# EasyEDA_Source.net
KiCad netlist of a schematic drawn in EasyEDA
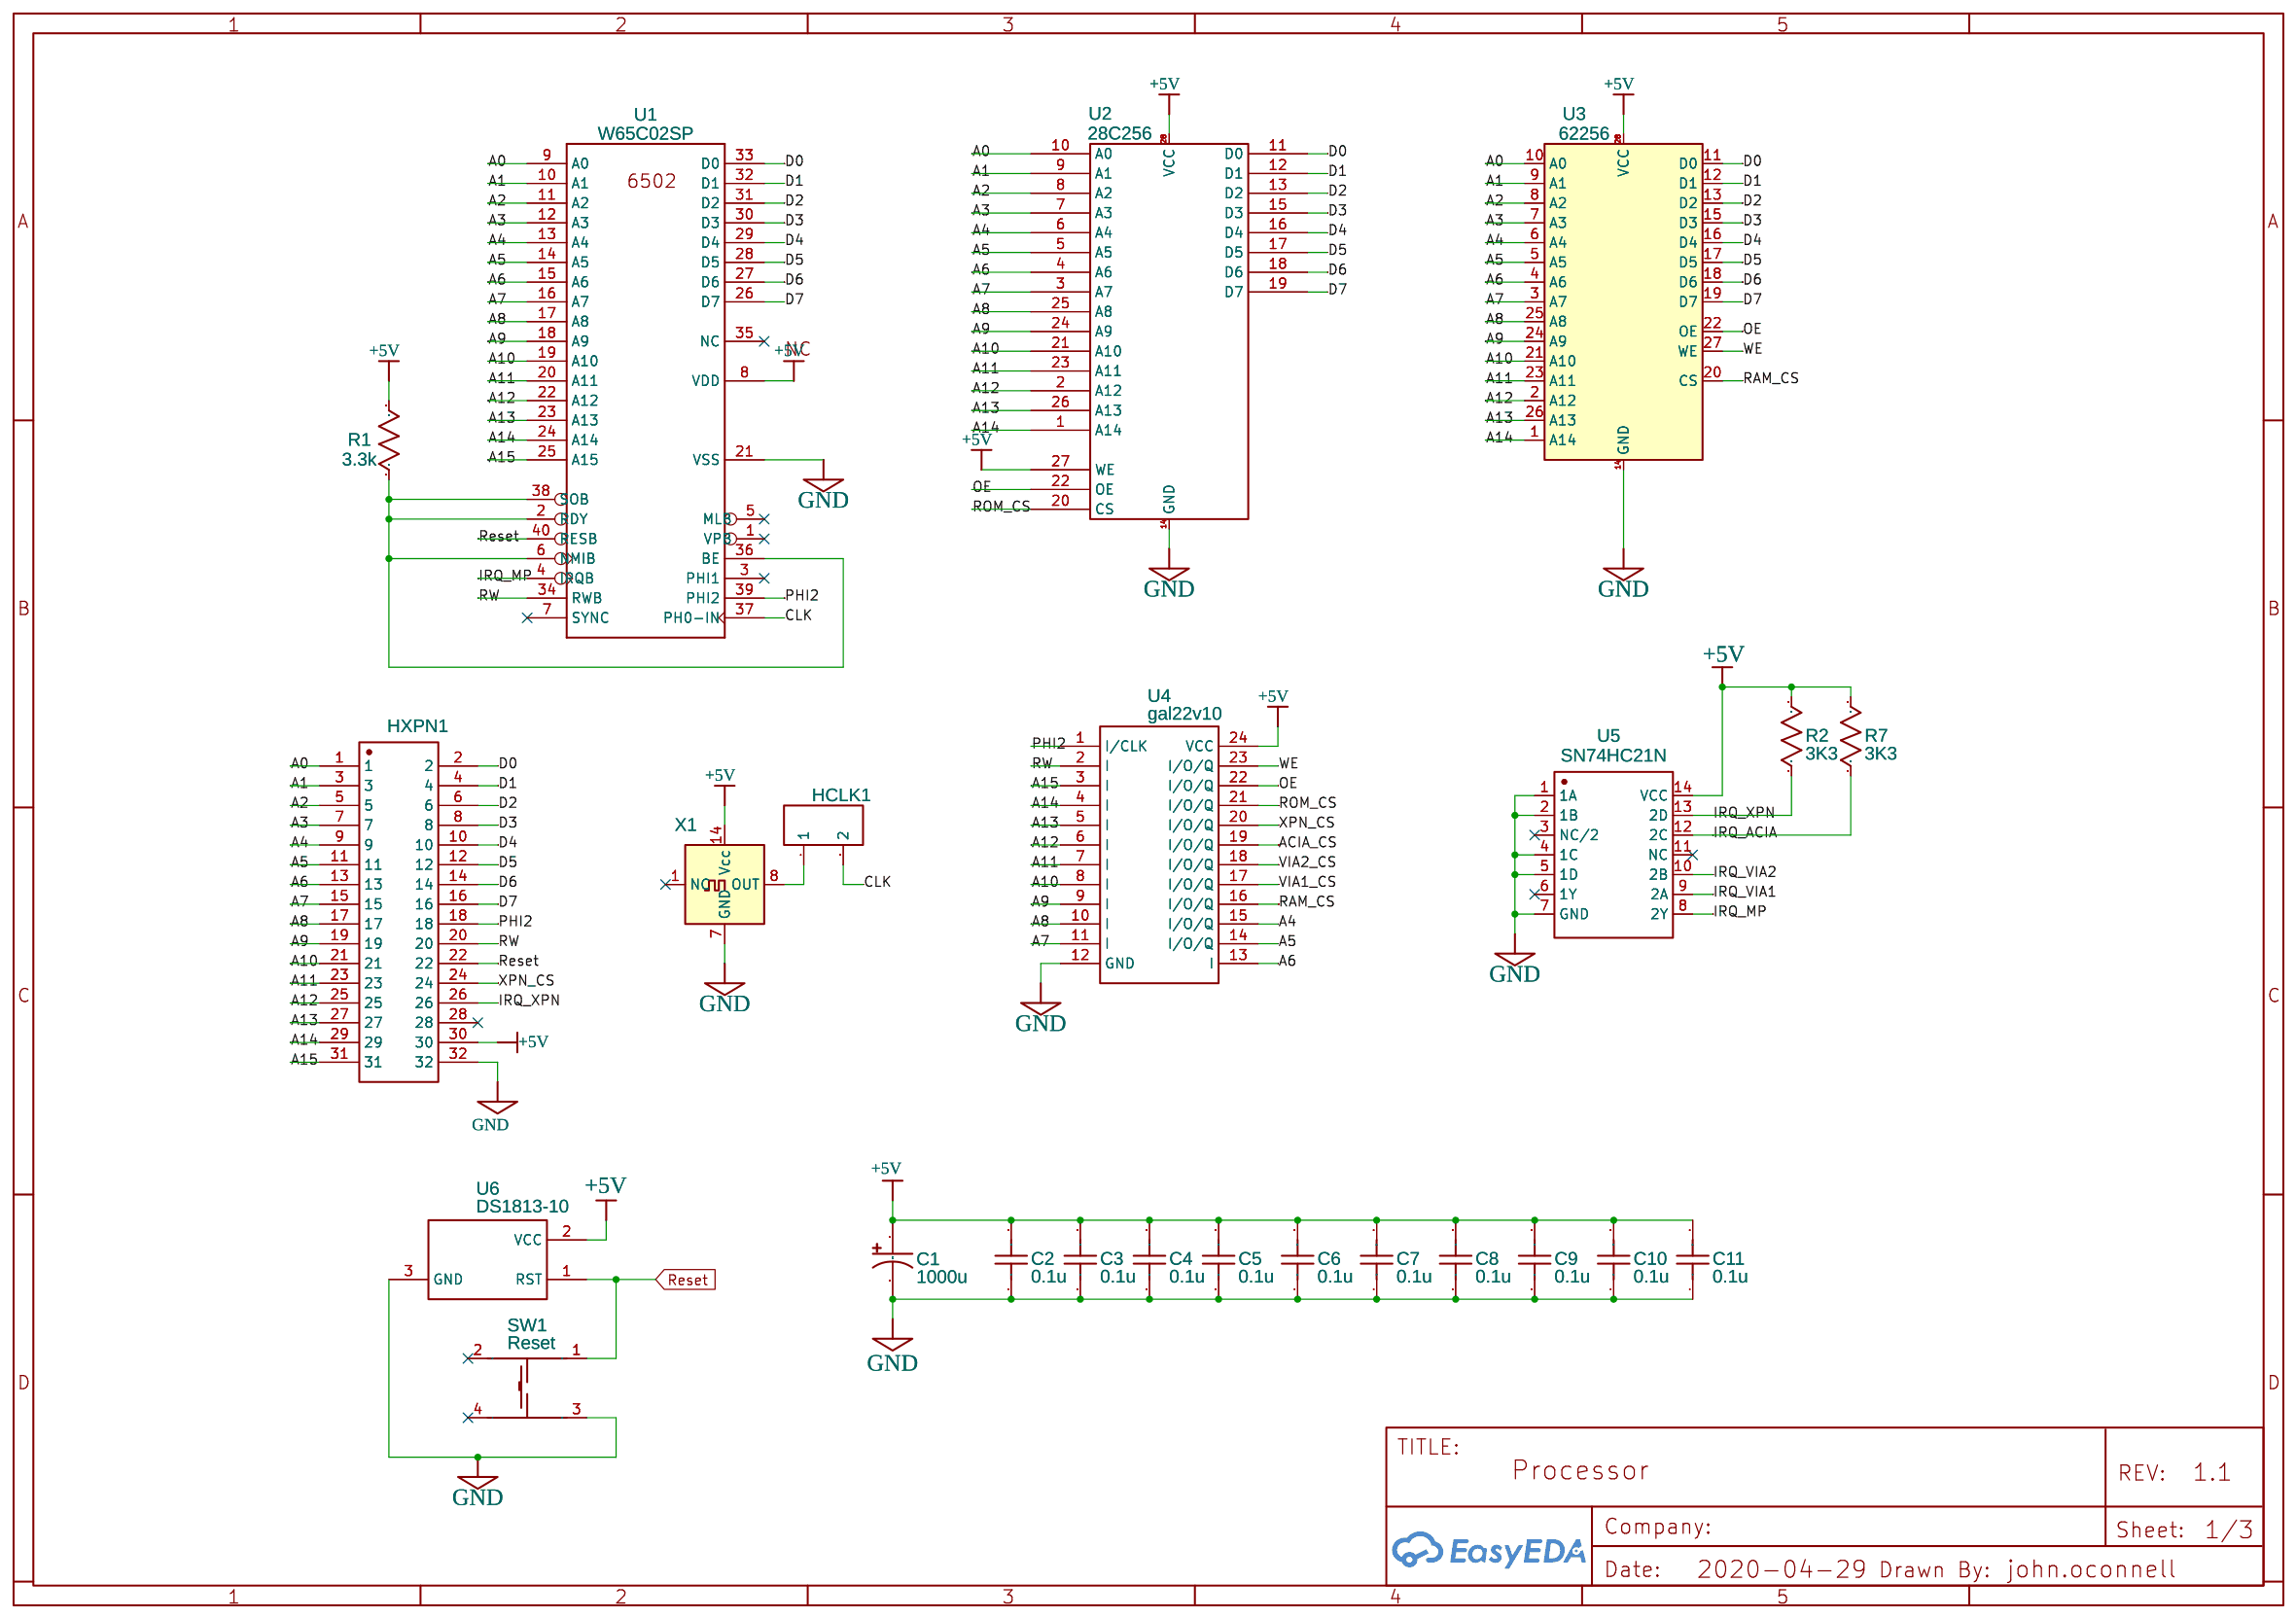
[diagram p0: Processor]
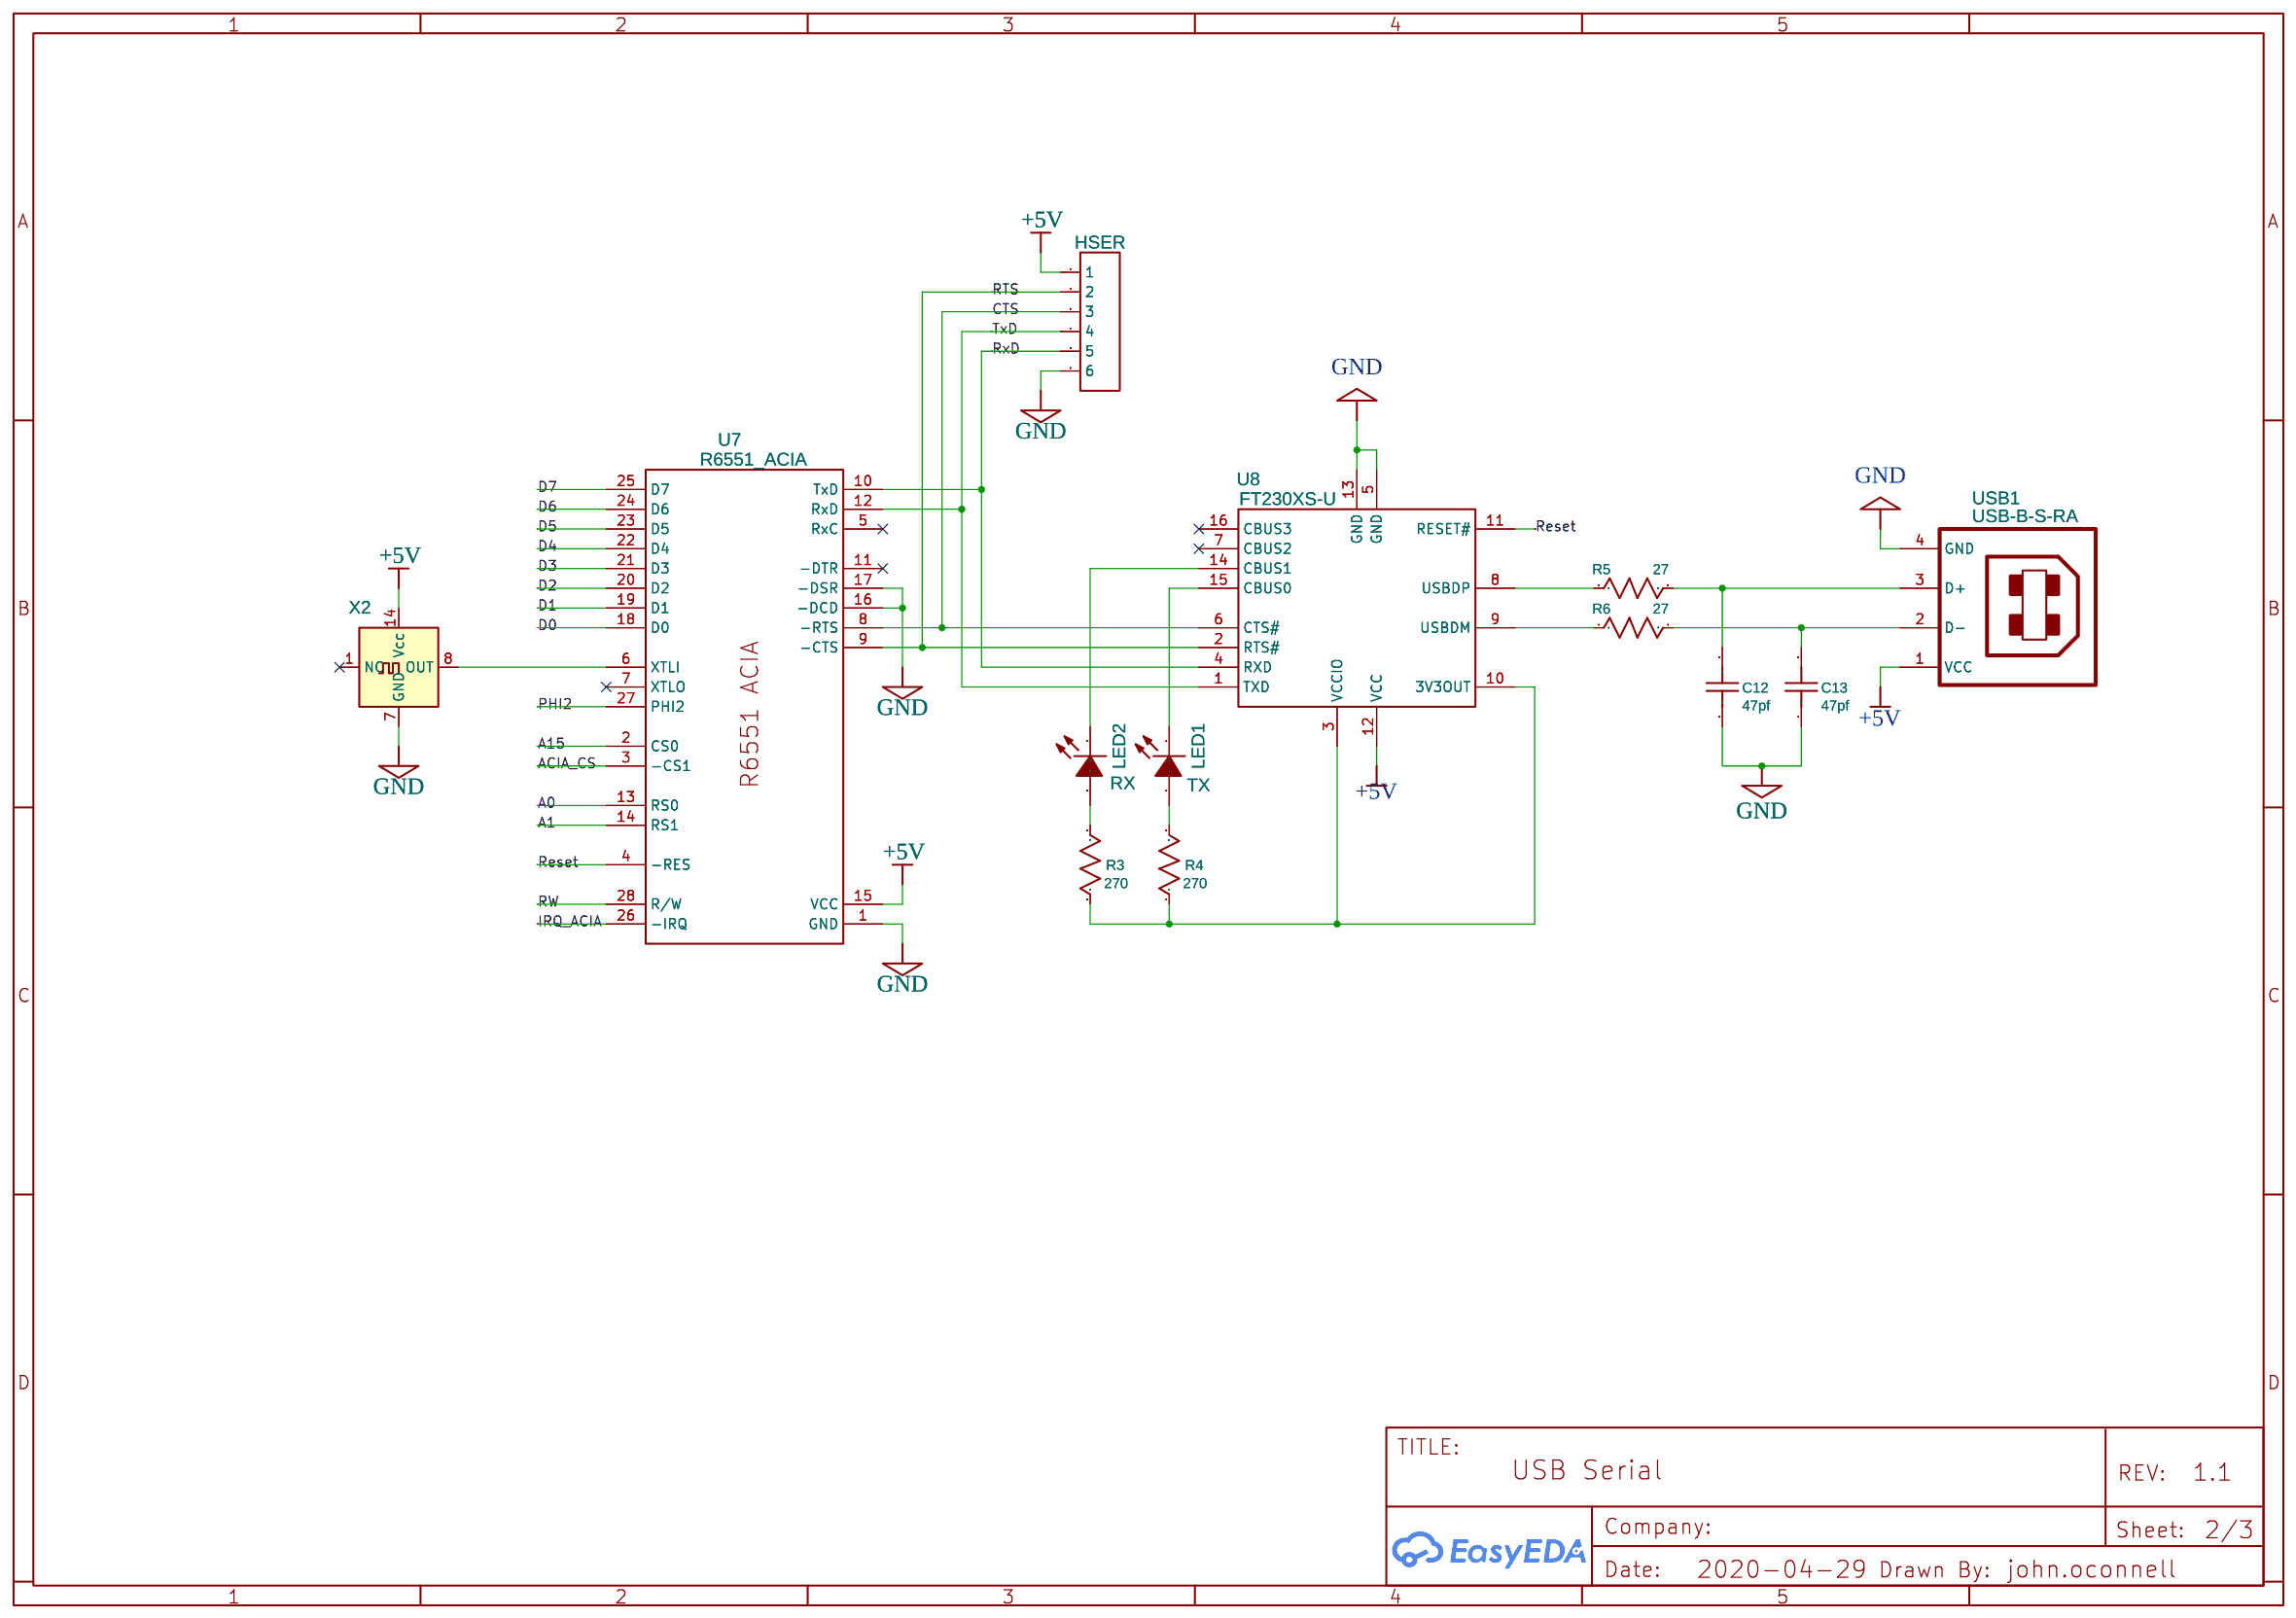
[diagram p1: USB Serial]
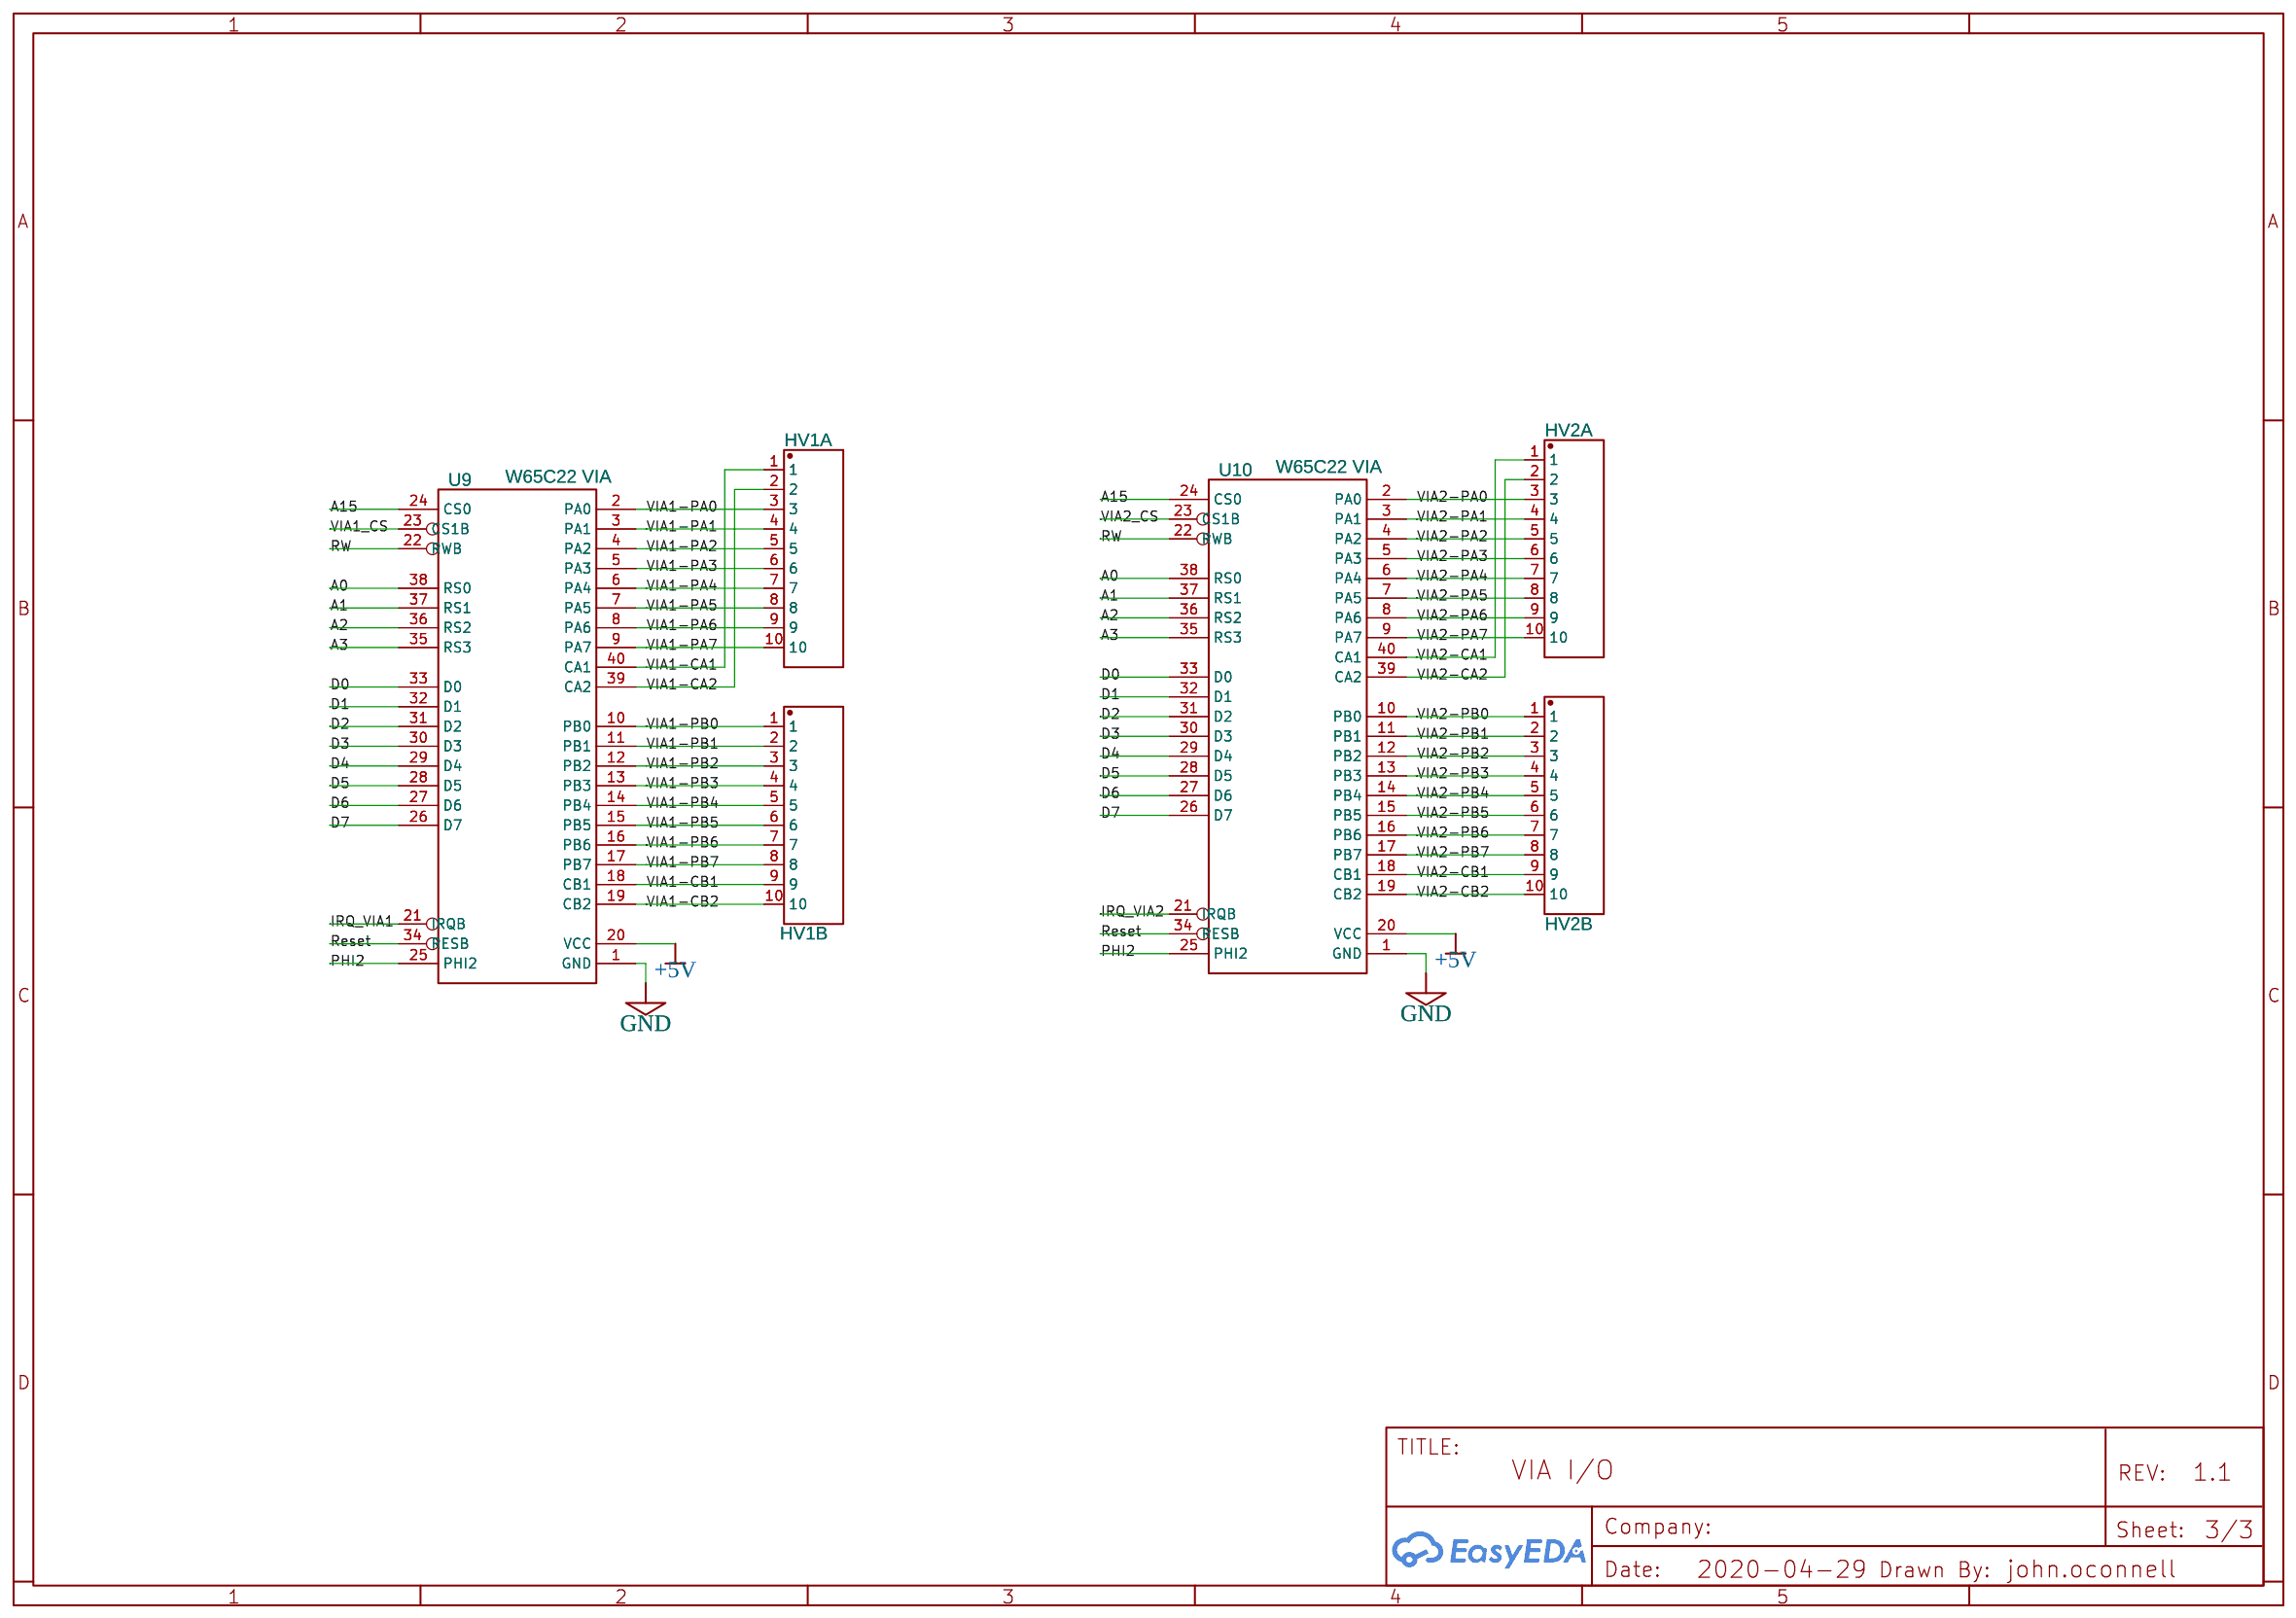
[diagram p2: VIA IO]

(export (version "E")
  (design (tool "Eeschema 10.0.6"))
  (components
    (comp (ref "C1") (value "1000u") (libsource (lib "") (part "Cap_Electrolytic(TH)_D3.0XF1.5_US")))
    (comp (ref "C2") (value "0.1u") (libsource (lib "") (part "Cap_RAD-0.1_US")))
    (comp (ref "C3") (value "0.1u") (libsource (lib "") (part "Cap_RAD-0.1_US")))
    (comp (ref "C4") (value "0.1u") (libsource (lib "") (part "Cap_RAD-0.1_US")))
    (comp (ref "C5") (value "0.1u") (libsource (lib "") (part "Cap_RAD-0.1_US")))
    (comp (ref "C6") (value "0.1u") (libsource (lib "") (part "Cap_RAD-0.1_US")))
    (comp (ref "C7") (value "0.1u") (libsource (lib "") (part "Cap_RAD-0.1_US")))
    (comp (ref "C8") (value "0.1u") (libsource (lib "") (part "Cap_RAD-0.1_US")))
    (comp (ref "C9") (value "0.1u") (libsource (lib "") (part "Cap_RAD-0.1_US")))
    (comp (ref "C10") (value "0.1u") (libsource (lib "") (part "Cap_RAD-0.1_US")))
    (comp (ref "C11") (value "0.1u") (libsource (lib "") (part "Cap_RAD-0.1_US")))
    (comp (ref "HCLK1")
      (value "Header-Male-2.54_1x2")
      (fields (field (name "BOM_Manufacturer Part") "826629-2") (field (name "BOM_Supplier Part") "C86471"))
      (libsource (lib "") (part "Header-Male-2.54_1x2"))
    )
    (comp (ref "HXPN1")
      (value "210S-2*16P L=11.6MMGold-plated black")
      (fields (field (name "BOM_Supplier Part") "C124382"))
      (libsource (lib "") (part "210S-2*16P L=11.6MMGold-plated black"))
    )
    (comp (ref "R1") (value "3.3k") (libsource (lib "") (part "Res_AXIAL-0.4(1/4W)_US")))
    (comp (ref "R2") (value "3K3") (libsource (lib "") (part "Res_AXIAL-0.4(1/4W)_US")))
    (comp (ref "R7") (value "3K3") (libsource (lib "") (part "Res_AXIAL-0.4(1/4W)_US")))
    (comp (ref "SW1")
      (value "Reset")
      (fields
        (field (name "BOM_Manufacturer Part") "K2-1102SP-C4SC-04")
        (field (name "BOM_Supplier Part") "C127509")
      )
      (libsource (lib "") (part "Unknown_260_-115"))
    )
    (comp (ref "U1") (value "W65C02SP") (libsource (lib "") (part "Unknown_330_-625")))
    (comp (ref "U2") (value "28C256") (libsource (lib "") (part "Unknown_585_-645")))
    (comp (ref "U3") (value "62256") (libsource (lib "") (part "Unknown_815_-660")))
    (comp (ref "U4") (value "gal22v10") (libsource (lib "") (part "gal22v10")))
    (comp (ref "U5") (value "SN74HC21N") (libsource (lib "") (part "SN74HC21N")))
    (comp (ref "U6") (value "DS1813-10") (libsource (lib "") (part "DS1813-10")))
    (comp (ref "X1") (value "1 MHZ") (libsource (lib "") (part "DGOF5S3")))
    (comp (ref "C12") (value "47pf") (libsource (lib "") (part "Cap_RAD-0.1_US")))
    (comp (ref "C13") (value "47pf") (libsource (lib "") (part "Cap_RAD-0.1_US")))
    (comp (ref "HSER")
      (value "Header-Male-2.54_1x6")
      (fields (field (name "BOM_Supplier Part") "C37208"))
      (libsource (lib "") (part "Header-Male-2.54_1x6"))
    )
    (comp (ref "LED1")
      (value "TX")
      (fields
        (field (name "BOM_Manufacturer Part") "204-10SURD/S530-A3")
        (field (name "BOM_Supplier Part") "C99772")
      )
      (libsource (lib "") (part "204-10SURD/S530-A3"))
    )
    (comp (ref "LED2")
      (value "RX")
      (fields
        (field (name "BOM_Manufacturer Part") "204-10SURD/S530-A3")
        (field (name "BOM_Supplier Part") "C99772")
      )
      (libsource (lib "") (part "204-10SURD/S530-A3"))
    )
    (comp (ref "R3") (value "270") (libsource (lib "") (part "Res_AXIAL-0.4(1/4W)_US")))
    (comp (ref "R4") (value "270") (libsource (lib "") (part "Res_AXIAL-0.4(1/4W)_US")))
    (comp (ref "R5") (value "27") (libsource (lib "") (part "Res_AXIAL-0.4(1/4W)_US_1")))
    (comp (ref "R6") (value "27") (libsource (lib "") (part "Res_AXIAL-0.4(1/4W)_US_1")))
    (comp (ref "U7")
      (value "R6551_ACIA")
      (fields (field (name "BOM_Manufacturer Part") "6551 ACIA"))
      (libsource (lib "") (part "R6551_ACIA"))
    )
    (comp (ref "U8")
      (value "FT230XS-U")
      (fields (field (name "BOM_Supplier Part") "C132162"))
      (libsource (lib "") (part "FT230XS-U"))
    )
    (comp (ref "USB1")
      (value "USB-B-S-RA")
      (fields (field (name "BOM_Supplier Part") "2112373"))
      (libsource (lib "") (part "USB-B-S-RA"))
    )
    (comp (ref "X2") (value "1.8432 MHZ") (libsource (lib "") (part "DGOF5S3")))
    (comp (ref "HV1A")
      (value "210S-1*10P L=11.6MMGold-plated black")
      (fields (field (name "BOM_Supplier Part") "C124372"))
      (libsource (lib "") (part "Unknown_400_-530"))
    )
    (comp (ref "HV1B")
      (value "210S-1*10P L=11.6MMGold-plated black")
      (fields (field (name "BOM_Supplier Part") "C124372"))
      (libsource (lib "") (part "Unknown_400_-400"))
    )
    (comp (ref "HV2A")
      (value "210S-1*10P L=11.6MMGold-plated black")
      (fields (field (name "BOM_Supplier Part") "C124372"))
      (libsource (lib "") (part "Unknown_785_-535"))
    )
    (comp (ref "HV2B")
      (value "210S-1*10P L=11.6MMGold-plated black")
      (fields (field (name "BOM_Supplier Part") "C124372"))
      (libsource (lib "") (part "Unknown_785_-405"))
    )
    (comp (ref "U9")
      (value "W65C22 VIA")
      (fields (field (name "BOM_Manufacturer Part") "6522"))
      (libsource (lib "") (part "Unknown_215_-565"))
    )
    (comp (ref "U10")
      (value "W65C22 VIA")
      (fields (field (name "BOM_Manufacturer Part") "6522"))
      (libsource (lib "") (part "Unknown_605_-570"))
    )
  )
  (nets
    (net (code "1") (name "+5V") (class "Default")
      (node (ref "C1") (pin "1") (pinfunction "1_1") (pintype "unspecified"))
      (node (ref "C10") (pin "2") (pinfunction "2_2") (pintype "unspecified"))
      (node (ref "C11") (pin "2") (pinfunction "2_2") (pintype "unspecified"))
      (node (ref "C2") (pin "2") (pinfunction "2_2") (pintype "unspecified"))
      (node (ref "C3") (pin "2") (pinfunction "2_2") (pintype "unspecified"))
      (node (ref "C4") (pin "2") (pinfunction "2_2") (pintype "unspecified"))
      (node (ref "C5") (pin "2") (pinfunction "2_2") (pintype "unspecified"))
      (node (ref "C6") (pin "2") (pinfunction "2_2") (pintype "unspecified"))
      (node (ref "C7") (pin "2") (pinfunction "2_2") (pintype "unspecified"))
      (node (ref "C8") (pin "2") (pinfunction "2_2") (pintype "unspecified"))
      (node (ref "C9") (pin "2") (pinfunction "2_2") (pintype "unspecified"))
      (node (ref "HSER") (pin "1") (pinfunction "1_1") (pintype "input"))
      (node (ref "HXPN1") (pin "30") (pinfunction "30_30") (pintype "unspecified"))
      (node (ref "R1") (pin "2") (pinfunction "2_2") (pintype "unspecified"))
      (node (ref "R2") (pin "2") (pinfunction "2_2") (pintype "unspecified"))
      (node (ref "R7") (pin "2") (pinfunction "2_2") (pintype "unspecified"))
      (node (ref "U1") (pin "8") (pinfunction "VDD_8") (pintype "passive"))
      (node (ref "U10") (pin "20") (pinfunction "VCC_20") (pintype "passive"))
      (node (ref "U2") (pin "27") (pinfunction "WE_27") (pintype "input"))
      (node (ref "U2") (pin "28") (pinfunction "VCC_28") (pintype "passive"))
      (node (ref "U3") (pin "28") (pinfunction "VCC_28") (pintype "passive"))
      (node (ref "U4") (pin "24") (pinfunction "VCC_24") (pintype "unspecified"))
      (node (ref "U5") (pin "14") (pinfunction "VCC_14") (pintype "unspecified"))
      (node (ref "U6") (pin "2") (pinfunction "VCC_2") (pintype "passive"))
      (node (ref "U7") (pin "15") (pinfunction "VCC_15") (pintype "unspecified"))
      (node (ref "U8") (pin "12") (pinfunction "VCC_12") (pintype "passive"))
      (node (ref "U9") (pin "20") (pinfunction "VCC_20") (pintype "passive"))
      (node (ref "USB1") (pin "1") (pinfunction "VCC_1") (pintype "input"))
      (node (ref "X1") (pin "14") (pinfunction "Vcc_14") (pintype "bidirectional"))
      (node (ref "X2") (pin "14") (pinfunction "Vcc_14") (pintype "bidirectional"))
    )
    (net (code "2") (name "A0") (class "Default")
      (node (ref "HXPN1") (pin "1") (pinfunction "1_1") (pintype "unspecified"))
      (node (ref "U1") (pin "9") (pinfunction "A0_9") (pintype "unspecified"))
      (node (ref "U10") (pin "38") (pinfunction "RS0_38") (pintype "unspecified"))
      (node (ref "U2") (pin "10") (pinfunction "A0_10") (pintype "input"))
      (node (ref "U3") (pin "10") (pinfunction "A0_10") (pintype "input"))
      (node (ref "U7") (pin "13") (pinfunction "RS0_13") (pintype "unspecified"))
      (node (ref "U9") (pin "38") (pinfunction "RS0_38") (pintype "unspecified"))
    )
    (net (code "3") (name "A1") (class "Default")
      (node (ref "HXPN1") (pin "3") (pinfunction "3_3") (pintype "unspecified"))
      (node (ref "U1") (pin "10") (pinfunction "A1_10") (pintype "unspecified"))
      (node (ref "U10") (pin "37") (pinfunction "RS1_37") (pintype "unspecified"))
      (node (ref "U2") (pin "9") (pinfunction "A1_9") (pintype "input"))
      (node (ref "U3") (pin "9") (pinfunction "A1_9") (pintype "input"))
      (node (ref "U7") (pin "14") (pinfunction "RS1_14") (pintype "unspecified"))
      (node (ref "U9") (pin "37") (pinfunction "RS1_37") (pintype "unspecified"))
    )
    (net (code "4") (name "A2") (class "Default")
      (node (ref "HXPN1") (pin "5") (pinfunction "5_5") (pintype "unspecified"))
      (node (ref "U1") (pin "11") (pinfunction "A2_11") (pintype "unspecified"))
      (node (ref "U10") (pin "36") (pinfunction "RS2_36") (pintype "unspecified"))
      (node (ref "U2") (pin "8") (pinfunction "A2_8") (pintype "input"))
      (node (ref "U3") (pin "8") (pinfunction "A2_8") (pintype "input"))
      (node (ref "U9") (pin "36") (pinfunction "RS2_36") (pintype "unspecified"))
    )
    (net (code "5") (name "A3") (class "Default")
      (node (ref "HXPN1") (pin "7") (pinfunction "7_7") (pintype "unspecified"))
      (node (ref "U1") (pin "12") (pinfunction "A3_12") (pintype "unspecified"))
      (node (ref "U10") (pin "35") (pinfunction "RS3_35") (pintype "unspecified"))
      (node (ref "U2") (pin "7") (pinfunction "A3_7") (pintype "input"))
      (node (ref "U3") (pin "7") (pinfunction "A3_7") (pintype "input"))
      (node (ref "U9") (pin "35") (pinfunction "RS3_35") (pintype "unspecified"))
    )
    (net (code "6") (name "A4") (class "Default")
      (node (ref "HXPN1") (pin "9") (pinfunction "9_9") (pintype "unspecified"))
      (node (ref "U1") (pin "13") (pinfunction "A4_13") (pintype "unspecified"))
      (node (ref "U2") (pin "6") (pinfunction "A4_6") (pintype "input"))
      (node (ref "U3") (pin "6") (pinfunction "A4_6") (pintype "input"))
      (node (ref "U4") (pin "15") (pinfunction "I/O/Q_15") (pintype "unspecified"))
    )
    (net (code "7") (name "A5") (class "Default")
      (node (ref "HXPN1") (pin "11") (pinfunction "11_11") (pintype "unspecified"))
      (node (ref "U1") (pin "14") (pinfunction "A5_14") (pintype "unspecified"))
      (node (ref "U2") (pin "5") (pinfunction "A5_5") (pintype "input"))
      (node (ref "U3") (pin "5") (pinfunction "A5_5") (pintype "input"))
      (node (ref "U4") (pin "14") (pinfunction "I/O/Q_14") (pintype "unspecified"))
    )
    (net (code "8") (name "A6") (class "Default")
      (node (ref "HXPN1") (pin "13") (pinfunction "13_13") (pintype "unspecified"))
      (node (ref "U1") (pin "15") (pinfunction "A6_15") (pintype "unspecified"))
      (node (ref "U2") (pin "4") (pinfunction "A6_4") (pintype "input"))
      (node (ref "U3") (pin "4") (pinfunction "A6_4") (pintype "input"))
      (node (ref "U4") (pin "13") (pinfunction "I_13") (pintype "unspecified"))
    )
    (net (code "9") (name "A7") (class "Default")
      (node (ref "HXPN1") (pin "15") (pinfunction "15_15") (pintype "unspecified"))
      (node (ref "U1") (pin "16") (pinfunction "A7_16") (pintype "unspecified"))
      (node (ref "U2") (pin "3") (pinfunction "A7_3") (pintype "input"))
      (node (ref "U3") (pin "3") (pinfunction "A7_3") (pintype "input"))
      (node (ref "U4") (pin "11") (pinfunction "I_11") (pintype "unspecified"))
    )
    (net (code "10") (name "A8") (class "Default")
      (node (ref "HXPN1") (pin "17") (pinfunction "17_17") (pintype "unspecified"))
      (node (ref "U1") (pin "17") (pinfunction "A8_17") (pintype "unspecified"))
      (node (ref "U2") (pin "25") (pinfunction "A8_25") (pintype "input"))
      (node (ref "U3") (pin "25") (pinfunction "A8_25") (pintype "input"))
      (node (ref "U4") (pin "10") (pinfunction "I_10") (pintype "unspecified"))
    )
    (net (code "11") (name "A9") (class "Default")
      (node (ref "HXPN1") (pin "19") (pinfunction "19_19") (pintype "unspecified"))
      (node (ref "U1") (pin "18") (pinfunction "A9_18") (pintype "unspecified"))
      (node (ref "U2") (pin "24") (pinfunction "A9_24") (pintype "input"))
      (node (ref "U3") (pin "24") (pinfunction "A9_24") (pintype "input"))
      (node (ref "U4") (pin "9") (pinfunction "I_9") (pintype "unspecified"))
    )
    (net (code "12") (name "A10") (class "Default")
      (node (ref "HXPN1") (pin "21") (pinfunction "21_21") (pintype "unspecified"))
      (node (ref "U1") (pin "19") (pinfunction "A10_19") (pintype "unspecified"))
      (node (ref "U2") (pin "21") (pinfunction "A10_21") (pintype "input"))
      (node (ref "U3") (pin "21") (pinfunction "A10_21") (pintype "input"))
      (node (ref "U4") (pin "8") (pinfunction "I_8") (pintype "unspecified"))
    )
    (net (code "13") (name "A11") (class "Default")
      (node (ref "HXPN1") (pin "23") (pinfunction "23_23") (pintype "unspecified"))
      (node (ref "U1") (pin "20") (pinfunction "A11_20") (pintype "unspecified"))
      (node (ref "U2") (pin "23") (pinfunction "A11_23") (pintype "input"))
      (node (ref "U3") (pin "23") (pinfunction "A11_23") (pintype "input"))
      (node (ref "U4") (pin "7") (pinfunction "I_7") (pintype "unspecified"))
    )
    (net (code "14") (name "A12") (class "Default")
      (node (ref "HXPN1") (pin "25") (pinfunction "25_25") (pintype "unspecified"))
      (node (ref "U1") (pin "22") (pinfunction "A12_22") (pintype "unspecified"))
      (node (ref "U2") (pin "2") (pinfunction "A12_2") (pintype "input"))
      (node (ref "U3") (pin "2") (pinfunction "A12_2") (pintype "input"))
      (node (ref "U4") (pin "6") (pinfunction "I_6") (pintype "unspecified"))
    )
    (net (code "15") (name "A13") (class "Default")
      (node (ref "HXPN1") (pin "27") (pinfunction "27_27") (pintype "unspecified"))
      (node (ref "U1") (pin "23") (pinfunction "A13_23") (pintype "unspecified"))
      (node (ref "U2") (pin "26") (pinfunction "A13_26") (pintype "input"))
      (node (ref "U3") (pin "26") (pinfunction "A13_26") (pintype "input"))
      (node (ref "U4") (pin "5") (pinfunction "I_5") (pintype "unspecified"))
    )
    (net (code "16") (name "A14") (class "Default")
      (node (ref "HXPN1") (pin "29") (pinfunction "29_29") (pintype "unspecified"))
      (node (ref "U1") (pin "24") (pinfunction "A14_24") (pintype "unspecified"))
      (node (ref "U2") (pin "1") (pinfunction "A14_1") (pintype "input"))
      (node (ref "U3") (pin "1") (pinfunction "A14_1") (pintype "input"))
      (node (ref "U4") (pin "4") (pinfunction "I_4") (pintype "unspecified"))
    )
    (net (code "17") (name "A15") (class "Default")
      (node (ref "HXPN1") (pin "31") (pinfunction "31_31") (pintype "unspecified"))
      (node (ref "U1") (pin "25") (pinfunction "A15_25") (pintype "unspecified"))
      (node (ref "U10") (pin "24") (pinfunction "CS0_24") (pintype "unspecified"))
      (node (ref "U4") (pin "3") (pinfunction "I_3") (pintype "unspecified"))
      (node (ref "U7") (pin "2") (pinfunction "CS0_2") (pintype "unspecified"))
      (node (ref "U9") (pin "24") (pinfunction "CS0_24") (pintype "unspecified"))
    )
    (net (code "18") (name "ACIA_CS") (class "Default")
      (node (ref "U4") (pin "19") (pinfunction "I/O/Q_19") (pintype "unspecified"))
      (node (ref "U7") (pin "3") (pinfunction "-CS1_3") (pintype "unspecified"))
    )
    (net (code "19") (name "CLK") (class "Default")
      (node (ref "HCLK1") (pin "2") (pinfunction "2_2") (pintype "unspecified"))
      (node (ref "U1") (pin "37") (pinfunction "PH0-IN_37") (pintype "input"))
    )
    (net (code "20") (name "CTS") (class "Default")
      (node (ref "HSER") (pin "3") (pinfunction "3_3") (pintype "input"))
      (node (ref "U7") (pin "8") (pinfunction "-RTS_8") (pintype "unspecified"))
      (node (ref "U8") (pin "6") (pinfunction "CTS#_6") (pintype "unspecified"))
    )
    (net (code "21") (name "D0") (class "Default")
      (node (ref "HXPN1") (pin "2") (pinfunction "2_2") (pintype "unspecified"))
      (node (ref "U1") (pin "33") (pinfunction "D0_33") (pintype "unspecified"))
      (node (ref "U10") (pin "33") (pinfunction "D0_33") (pintype "unspecified"))
      (node (ref "U2") (pin "11") (pinfunction "D0_11") (pintype "bidirectional"))
      (node (ref "U3") (pin "11") (pinfunction "D0_11") (pintype "bidirectional"))
      (node (ref "U7") (pin "18") (pinfunction "D0_18") (pintype "unspecified"))
      (node (ref "U9") (pin "33") (pinfunction "D0_33") (pintype "unspecified"))
    )
    (net (code "22") (name "D1") (class "Default")
      (node (ref "HXPN1") (pin "4") (pinfunction "4_4") (pintype "unspecified"))
      (node (ref "U1") (pin "32") (pinfunction "D1_32") (pintype "unspecified"))
      (node (ref "U10") (pin "32") (pinfunction "D1_32") (pintype "unspecified"))
      (node (ref "U2") (pin "12") (pinfunction "D1_12") (pintype "bidirectional"))
      (node (ref "U3") (pin "12") (pinfunction "D1_12") (pintype "bidirectional"))
      (node (ref "U7") (pin "19") (pinfunction "D1_19") (pintype "unspecified"))
      (node (ref "U9") (pin "32") (pinfunction "D1_32") (pintype "unspecified"))
    )
    (net (code "23") (name "D2") (class "Default")
      (node (ref "HXPN1") (pin "6") (pinfunction "6_6") (pintype "unspecified"))
      (node (ref "U1") (pin "31") (pinfunction "D2_31") (pintype "unspecified"))
      (node (ref "U10") (pin "31") (pinfunction "D2_31") (pintype "unspecified"))
      (node (ref "U2") (pin "13") (pinfunction "D2_13") (pintype "bidirectional"))
      (node (ref "U3") (pin "13") (pinfunction "D2_13") (pintype "bidirectional"))
      (node (ref "U7") (pin "20") (pinfunction "D2_20") (pintype "unspecified"))
      (node (ref "U9") (pin "31") (pinfunction "D2_31") (pintype "unspecified"))
    )
    (net (code "24") (name "D3") (class "Default")
      (node (ref "HXPN1") (pin "8") (pinfunction "8_8") (pintype "unspecified"))
      (node (ref "U1") (pin "30") (pinfunction "D3_30") (pintype "unspecified"))
      (node (ref "U10") (pin "30") (pinfunction "D3_30") (pintype "unspecified"))
      (node (ref "U2") (pin "15") (pinfunction "D3_15") (pintype "bidirectional"))
      (node (ref "U3") (pin "15") (pinfunction "D3_15") (pintype "bidirectional"))
      (node (ref "U7") (pin "21") (pinfunction "D3_21") (pintype "unspecified"))
      (node (ref "U9") (pin "30") (pinfunction "D3_30") (pintype "unspecified"))
    )
    (net (code "25") (name "D4") (class "Default")
      (node (ref "HXPN1") (pin "10") (pinfunction "10_10") (pintype "unspecified"))
      (node (ref "U1") (pin "29") (pinfunction "D4_29") (pintype "unspecified"))
      (node (ref "U10") (pin "29") (pinfunction "D4_29") (pintype "unspecified"))
      (node (ref "U2") (pin "16") (pinfunction "D4_16") (pintype "bidirectional"))
      (node (ref "U3") (pin "16") (pinfunction "D4_16") (pintype "bidirectional"))
      (node (ref "U7") (pin "22") (pinfunction "D4_22") (pintype "unspecified"))
      (node (ref "U9") (pin "29") (pinfunction "D4_29") (pintype "unspecified"))
    )
    (net (code "26") (name "D5") (class "Default")
      (node (ref "HXPN1") (pin "12") (pinfunction "12_12") (pintype "unspecified"))
      (node (ref "U1") (pin "28") (pinfunction "D5_28") (pintype "unspecified"))
      (node (ref "U10") (pin "28") (pinfunction "D5_28") (pintype "unspecified"))
      (node (ref "U2") (pin "17") (pinfunction "D5_17") (pintype "bidirectional"))
      (node (ref "U3") (pin "17") (pinfunction "D5_17") (pintype "bidirectional"))
      (node (ref "U7") (pin "23") (pinfunction "D5_23") (pintype "unspecified"))
      (node (ref "U9") (pin "28") (pinfunction "D5_28") (pintype "unspecified"))
    )
    (net (code "27") (name "D6") (class "Default")
      (node (ref "HXPN1") (pin "14") (pinfunction "14_14") (pintype "unspecified"))
      (node (ref "U1") (pin "27") (pinfunction "D6_27") (pintype "unspecified"))
      (node (ref "U10") (pin "27") (pinfunction "D6_27") (pintype "unspecified"))
      (node (ref "U2") (pin "18") (pinfunction "D6_18") (pintype "bidirectional"))
      (node (ref "U3") (pin "18") (pinfunction "D6_18") (pintype "bidirectional"))
      (node (ref "U7") (pin "24") (pinfunction "D6_24") (pintype "unspecified"))
      (node (ref "U9") (pin "27") (pinfunction "D6_27") (pintype "unspecified"))
    )
    (net (code "28") (name "D7") (class "Default")
      (node (ref "HXPN1") (pin "16") (pinfunction "16_16") (pintype "unspecified"))
      (node (ref "U1") (pin "26") (pinfunction "D7_26") (pintype "unspecified"))
      (node (ref "U10") (pin "26") (pinfunction "D7_26") (pintype "unspecified"))
      (node (ref "U2") (pin "19") (pinfunction "D7_19") (pintype "bidirectional"))
      (node (ref "U3") (pin "19") (pinfunction "D7_19") (pintype "bidirectional"))
      (node (ref "U7") (pin "25") (pinfunction "D7_25") (pintype "unspecified"))
      (node (ref "U9") (pin "26") (pinfunction "D7_26") (pintype "unspecified"))
    )
    (net (code "29") (name "GND") (class "Default")
      (node (ref "C1") (pin "2") (pinfunction "2_2") (pintype "unspecified"))
      (node (ref "C10") (pin "1") (pinfunction "1_1") (pintype "unspecified"))
      (node (ref "C11") (pin "1") (pinfunction "1_1") (pintype "unspecified"))
      (node (ref "C12") (pin "1") (pinfunction "1_1") (pintype "unspecified"))
      (node (ref "C13") (pin "1") (pinfunction "1_1") (pintype "unspecified"))
      (node (ref "C2") (pin "1") (pinfunction "1_1") (pintype "unspecified"))
      (node (ref "C3") (pin "1") (pinfunction "1_1") (pintype "unspecified"))
      (node (ref "C4") (pin "1") (pinfunction "1_1") (pintype "unspecified"))
      (node (ref "C5") (pin "1") (pinfunction "1_1") (pintype "unspecified"))
      (node (ref "C6") (pin "1") (pinfunction "1_1") (pintype "unspecified"))
      (node (ref "C7") (pin "1") (pinfunction "1_1") (pintype "unspecified"))
      (node (ref "C8") (pin "1") (pinfunction "1_1") (pintype "unspecified"))
      (node (ref "C9") (pin "1") (pinfunction "1_1") (pintype "unspecified"))
      (node (ref "HSER") (pin "6") (pinfunction "6_6") (pintype "input"))
      (node (ref "HXPN1") (pin "32") (pinfunction "32_32") (pintype "unspecified"))
      (node (ref "SW1") (pin "3") (pinfunction "3_3") (pintype "unspecified"))
      (node (ref "U1") (pin "21") (pinfunction "VSS_21") (pintype "unspecified"))
      (node (ref "U10") (pin "1") (pinfunction "GND_1") (pintype "passive"))
      (node (ref "U2") (pin "14") (pinfunction "GND_14") (pintype "passive"))
      (node (ref "U3") (pin "14") (pinfunction "GND_14") (pintype "passive"))
      (node (ref "U4") (pin "12") (pinfunction "GND_12") (pintype "unspecified"))
      (node (ref "U5") (pin "1") (pinfunction "1A_1") (pintype "unspecified"))
      (node (ref "U5") (pin "2") (pinfunction "1B_2") (pintype "unspecified"))
      (node (ref "U5") (pin "4") (pinfunction "1C_4") (pintype "unspecified"))
      (node (ref "U5") (pin "5") (pinfunction "1D_5") (pintype "unspecified"))
      (node (ref "U5") (pin "7") (pinfunction "GND_7") (pintype "unspecified"))
      (node (ref "U6") (pin "3") (pinfunction "GND_3") (pintype "passive"))
      (node (ref "U7") (pin "1") (pinfunction "GND_1") (pintype "unspecified"))
      (node (ref "U7") (pin "16") (pinfunction "-DCD_16") (pintype "unspecified"))
      (node (ref "U7") (pin "17") (pinfunction "-DSR_17") (pintype "unspecified"))
      (node (ref "U8") (pin "13") (pinfunction "GND_13") (pintype "passive"))
      (node (ref "U8") (pin "5") (pinfunction "GND_5") (pintype "passive"))
      (node (ref "U9") (pin "1") (pinfunction "GND_1") (pintype "passive"))
      (node (ref "USB1") (pin "4") (pinfunction "GND_4") (pintype "input"))
      (node (ref "X1") (pin "7") (pinfunction "GND_7") (pintype "bidirectional"))
      (node (ref "X2") (pin "7") (pinfunction "GND_7") (pintype "bidirectional"))
    )
    (net (code "30") (name "IRQ_ACIA") (class "Default")
      (node (ref "R7") (pin "1") (pinfunction "1_1") (pintype "unspecified"))
      (node (ref "U5") (pin "12") (pinfunction "2C_12") (pintype "unspecified"))
      (node (ref "U7") (pin "26") (pinfunction "-IRQ_26") (pintype "unspecified"))
    )
    (net (code "31") (name "IRQ_MP") (class "Default")
      (node (ref "U1") (pin "4") (pinfunction "IRQB_4") (pintype "input"))
      (node (ref "U5") (pin "8") (pinfunction "2Y_8") (pintype "unspecified"))
    )
    (net (code "32") (name "IRQ_VIA1") (class "Default")
      (node (ref "U5") (pin "9") (pinfunction "2A_9") (pintype "unspecified"))
      (node (ref "U9") (pin "21") (pinfunction "IRQB_21") (pintype "unspecified"))
    )
    (net (code "33") (name "IRQ_VIA2") (class "Default")
      (node (ref "U10") (pin "21") (pinfunction "IRQB_21") (pintype "unspecified"))
      (node (ref "U5") (pin "10") (pinfunction "2B_10") (pintype "unspecified"))
    )
    (net (code "34") (name "IRQ_XPN") (class "Default")
      (node (ref "HXPN1") (pin "26") (pinfunction "26_26") (pintype "unspecified"))
      (node (ref "R2") (pin "1") (pinfunction "1_1") (pintype "unspecified"))
      (node (ref "U5") (pin "13") (pinfunction "2D_13") (pintype "unspecified"))
    )
    (net (code "35") (name "Net-(LED1-A)") (class "Default")
      (node (ref "LED1") (pin "1") (pinfunction "A_1") (pintype "unspecified"))
      (node (ref "R4") (pin "2") (pinfunction "2_2") (pintype "unspecified"))
    )
    (net (code "36") (name "Net-(LED1-K)") (class "Default")
      (node (ref "LED1") (pin "2") (pinfunction "K_2") (pintype "unspecified"))
      (node (ref "U8") (pin "15") (pinfunction "CBUS0_15") (pintype "bidirectional"))
    )
    (net (code "37") (name "Net-(LED2-A)") (class "Default")
      (node (ref "LED2") (pin "1") (pinfunction "A_1") (pintype "unspecified"))
      (node (ref "R3") (pin "2") (pinfunction "2_2") (pintype "unspecified"))
    )
    (net (code "38") (name "Net-(LED2-K)") (class "Default")
      (node (ref "LED2") (pin "2") (pinfunction "K_2") (pintype "unspecified"))
      (node (ref "U8") (pin "14") (pinfunction "CBUS1_14") (pintype "bidirectional"))
    )
    (net (code "39") (name "Net-(U1-BE)") (class "Default")
      (node (ref "R1") (pin "1") (pinfunction "1_1") (pintype "unspecified"))
      (node (ref "U1") (pin "2") (pinfunction "RDY_2") (pintype "unspecified"))
      (node (ref "U1") (pin "36") (pinfunction "BE_36") (pintype "input"))
      (node (ref "U1") (pin "38") (pinfunction "SOB_38") (pintype "input"))
      (node (ref "U1") (pin "6") (pinfunction "NMIB_6") (pintype "input"))
    )
    (net (code "40") (name "Net-(U7-XTLI)") (class "Default")
      (node (ref "U7") (pin "6") (pinfunction "XTLI_6") (pintype "unspecified"))
      (node (ref "X2") (pin "8") (pinfunction "OUT_8") (pintype "output"))
    )
    (net (code "41") (name "Net-(U8-3V3OUT)") (class "Default")
      (node (ref "R3") (pin "1") (pinfunction "1_1") (pintype "unspecified"))
      (node (ref "R4") (pin "1") (pinfunction "1_1") (pintype "unspecified"))
      (node (ref "U8") (pin "10") (pinfunction "3V3OUT_10") (pintype "passive"))
      (node (ref "U8") (pin "3") (pinfunction "VCCIO_3") (pintype "passive"))
    )
    (net (code "42") (name "Net-(U8-USBDM)") (class "Default")
      (node (ref "R6") (pin "1") (pinfunction "1_1") (pintype "unspecified"))
      (node (ref "U8") (pin "9") (pinfunction "USBDM_9") (pintype "unspecified"))
    )
    (net (code "43") (name "Net-(U8-USBDP)") (class "Default")
      (node (ref "R5") (pin "1") (pinfunction "1_1") (pintype "unspecified"))
      (node (ref "U8") (pin "8") (pinfunction "USBDP_8") (pintype "unspecified"))
    )
    (net (code "44") (name "Net-(USB1-D+)") (class "Default")
      (node (ref "C12") (pin "2") (pinfunction "2_2") (pintype "unspecified"))
      (node (ref "R5") (pin "2") (pinfunction "2_2") (pintype "unspecified"))
      (node (ref "USB1") (pin "3") (pinfunction "D+_3") (pintype "input"))
    )
    (net (code "45") (name "Net-(USB1-D-)") (class "Default")
      (node (ref "C13") (pin "2") (pinfunction "2_2") (pintype "unspecified"))
      (node (ref "R6") (pin "2") (pinfunction "2_2") (pintype "unspecified"))
      (node (ref "USB1") (pin "2") (pinfunction "D-_2") (pintype "input"))
    )
    (net (code "46") (name "Net-(X1-OUT)") (class "Default")
      (node (ref "HCLK1") (pin "1") (pinfunction "1_1") (pintype "unspecified"))
      (node (ref "X1") (pin "8") (pinfunction "OUT_8") (pintype "output"))
    )
    (net (code "47") (name "OE") (class "Default")
      (node (ref "U2") (pin "22") (pinfunction "OE_22") (pintype "input"))
      (node (ref "U3") (pin "22") (pinfunction "OE_22") (pintype "input"))
      (node (ref "U4") (pin "22") (pinfunction "I/O/Q_22") (pintype "unspecified"))
    )
    (net (code "48") (name "PHI2") (class "Default")
      (node (ref "HXPN1") (pin "18") (pinfunction "18_18") (pintype "unspecified"))
      (node (ref "U1") (pin "39") (pinfunction "PHI2_39") (pintype "output"))
      (node (ref "U10") (pin "25") (pinfunction "PHI2_25") (pintype "unspecified"))
      (node (ref "U4") (pin "1") (pinfunction "I/CLK_1") (pintype "unspecified"))
      (node (ref "U7") (pin "27") (pinfunction "PHI2_27") (pintype "unspecified"))
      (node (ref "U9") (pin "25") (pinfunction "PHI2_25") (pintype "unspecified"))
    )
    (net (code "49") (name "RAM_CS") (class "Default")
      (node (ref "U3") (pin "20") (pinfunction "CS_20") (pintype "input"))
      (node (ref "U4") (pin "16") (pinfunction "I/O/Q_16") (pintype "unspecified"))
    )
    (net (code "50") (name "ROM_CS") (class "Default")
      (node (ref "U2") (pin "20") (pinfunction "CS_20") (pintype "input"))
      (node (ref "U4") (pin "21") (pinfunction "I/O/Q_21") (pintype "unspecified"))
    )
    (net (code "51") (name "RTS") (class "Default")
      (node (ref "HSER") (pin "2") (pinfunction "2_2") (pintype "input"))
      (node (ref "U7") (pin "9") (pinfunction "-CTS_9") (pintype "unspecified"))
      (node (ref "U8") (pin "2") (pinfunction "RTS#_2") (pintype "output"))
    )
    (net (code "52") (name "RW") (class "Default")
      (node (ref "HXPN1") (pin "20") (pinfunction "20_20") (pintype "unspecified"))
      (node (ref "U1") (pin "34") (pinfunction "RWB_34") (pintype "output"))
      (node (ref "U10") (pin "22") (pinfunction "RWB_22") (pintype "unspecified"))
      (node (ref "U4") (pin "2") (pinfunction "I_2") (pintype "unspecified"))
      (node (ref "U7") (pin "28") (pinfunction "R/W_28") (pintype "unspecified"))
      (node (ref "U9") (pin "22") (pinfunction "RWB_22") (pintype "unspecified"))
    )
    (net (code "53") (name "Reset") (class "Default")
      (node (ref "HXPN1") (pin "22") (pinfunction "22_22") (pintype "unspecified"))
      (node (ref "SW1") (pin "1") (pinfunction "1_1") (pintype "unspecified"))
      (node (ref "U1") (pin "40") (pinfunction "RESB_40") (pintype "input"))
      (node (ref "U10") (pin "34") (pinfunction "RESB_34") (pintype "unspecified"))
      (node (ref "U6") (pin "1") (pinfunction "RST_1") (pintype "output"))
      (node (ref "U7") (pin "4") (pinfunction "-RES_4") (pintype "unspecified"))
      (node (ref "U8") (pin "11") (pinfunction "RESET#_11") (pintype "unspecified"))
      (node (ref "U9") (pin "34") (pinfunction "RESB_34") (pintype "unspecified"))
    )
    (net (code "54") (name "RxD") (class "Default")
      (node (ref "HSER") (pin "5") (pinfunction "5_5") (pintype "input"))
      (node (ref "U7") (pin "10") (pinfunction "TxD_10") (pintype "unspecified"))
      (node (ref "U8") (pin "4") (pinfunction "RXD_4") (pintype "unspecified"))
    )
    (net (code "55") (name "TxD") (class "Default")
      (node (ref "HSER") (pin "4") (pinfunction "4_4") (pintype "input"))
      (node (ref "U7") (pin "12") (pinfunction "RxD_12") (pintype "unspecified"))
      (node (ref "U8") (pin "1") (pinfunction "TXD_1") (pintype "output"))
    )
    (net (code "56") (name "VIA1-CA1") (class "Default")
      (node (ref "HV1A") (pin "1") (pinfunction "1_1") (pintype "unspecified"))
      (node (ref "U9") (pin "40") (pinfunction "CA1_40") (pintype "unspecified"))
    )
    (net (code "57") (name "VIA1-CA2") (class "Default")
      (node (ref "HV1A") (pin "2") (pinfunction "2_2") (pintype "unspecified"))
      (node (ref "U9") (pin "39") (pinfunction "CA2_39") (pintype "unspecified"))
    )
    (net (code "58") (name "VIA1-CB1") (class "Default")
      (node (ref "HV1B") (pin "9") (pinfunction "9_9") (pintype "unspecified"))
      (node (ref "U9") (pin "18") (pinfunction "CB1_18") (pintype "unspecified"))
    )
    (net (code "59") (name "VIA1-CB2") (class "Default")
      (node (ref "HV1B") (pin "10") (pinfunction "10_10") (pintype "unspecified"))
      (node (ref "U9") (pin "19") (pinfunction "CB2_19") (pintype "unspecified"))
    )
    (net (code "60") (name "VIA1-PA0") (class "Default")
      (node (ref "HV1A") (pin "3") (pinfunction "3_3") (pintype "unspecified"))
      (node (ref "U9") (pin "2") (pinfunction "PA0_2") (pintype "unspecified"))
    )
    (net (code "61") (name "VIA1-PA1") (class "Default")
      (node (ref "HV1A") (pin "4") (pinfunction "4_4") (pintype "unspecified"))
      (node (ref "U9") (pin "3") (pinfunction "PA1_3") (pintype "unspecified"))
    )
    (net (code "62") (name "VIA1-PA2") (class "Default")
      (node (ref "HV1A") (pin "5") (pinfunction "5_5") (pintype "unspecified"))
      (node (ref "U9") (pin "4") (pinfunction "PA2_4") (pintype "unspecified"))
    )
    (net (code "63") (name "VIA1-PA3") (class "Default")
      (node (ref "HV1A") (pin "6") (pinfunction "6_6") (pintype "unspecified"))
      (node (ref "U9") (pin "5") (pinfunction "PA3_5") (pintype "unspecified"))
    )
    (net (code "64") (name "VIA1-PA4") (class "Default")
      (node (ref "HV1A") (pin "7") (pinfunction "7_7") (pintype "unspecified"))
      (node (ref "U9") (pin "6") (pinfunction "PA4_6") (pintype "unspecified"))
    )
    (net (code "65") (name "VIA1-PA5") (class "Default")
      (node (ref "HV1A") (pin "8") (pinfunction "8_8") (pintype "unspecified"))
      (node (ref "U9") (pin "7") (pinfunction "PA5_7") (pintype "unspecified"))
    )
    (net (code "66") (name "VIA1-PA6") (class "Default")
      (node (ref "HV1A") (pin "9") (pinfunction "9_9") (pintype "unspecified"))
      (node (ref "U9") (pin "8") (pinfunction "PA6_8") (pintype "unspecified"))
    )
    (net (code "67") (name "VIA1-PA7") (class "Default")
      (node (ref "HV1A") (pin "10") (pinfunction "10_10") (pintype "unspecified"))
      (node (ref "U9") (pin "9") (pinfunction "PA7_9") (pintype "unspecified"))
    )
    (net (code "68") (name "VIA1-PB0") (class "Default")
      (node (ref "HV1B") (pin "1") (pinfunction "1_1") (pintype "unspecified"))
      (node (ref "U9") (pin "10") (pinfunction "PB0_10") (pintype "unspecified"))
    )
    (net (code "69") (name "VIA1-PB1") (class "Default")
      (node (ref "HV1B") (pin "2") (pinfunction "2_2") (pintype "unspecified"))
      (node (ref "U9") (pin "11") (pinfunction "PB1_11") (pintype "unspecified"))
    )
    (net (code "70") (name "VIA1-PB2") (class "Default")
      (node (ref "HV1B") (pin "3") (pinfunction "3_3") (pintype "unspecified"))
      (node (ref "U9") (pin "12") (pinfunction "PB2_12") (pintype "unspecified"))
    )
    (net (code "71") (name "VIA1-PB3") (class "Default")
      (node (ref "HV1B") (pin "4") (pinfunction "4_4") (pintype "unspecified"))
      (node (ref "U9") (pin "13") (pinfunction "PB3_13") (pintype "unspecified"))
    )
    (net (code "72") (name "VIA1-PB4") (class "Default")
      (node (ref "HV1B") (pin "5") (pinfunction "5_5") (pintype "unspecified"))
      (node (ref "U9") (pin "14") (pinfunction "PB4_14") (pintype "unspecified"))
    )
    (net (code "73") (name "VIA1-PB5") (class "Default")
      (node (ref "HV1B") (pin "6") (pinfunction "6_6") (pintype "unspecified"))
      (node (ref "U9") (pin "15") (pinfunction "PB5_15") (pintype "unspecified"))
    )
    (net (code "74") (name "VIA1-PB6") (class "Default")
      (node (ref "HV1B") (pin "7") (pinfunction "7_7") (pintype "unspecified"))
      (node (ref "U9") (pin "16") (pinfunction "PB6_16") (pintype "unspecified"))
    )
    (net (code "75") (name "VIA1-PB7") (class "Default")
      (node (ref "HV1B") (pin "8") (pinfunction "8_8") (pintype "unspecified"))
      (node (ref "U9") (pin "17") (pinfunction "PB7_17") (pintype "unspecified"))
    )
    (net (code "76") (name "VIA1_CS") (class "Default")
      (node (ref "U4") (pin "17") (pinfunction "I/O/Q_17") (pintype "unspecified"))
      (node (ref "U9") (pin "23") (pinfunction "CS1B_23") (pintype "unspecified"))
    )
    (net (code "77") (name "VIA2-CA1") (class "Default")
      (node (ref "HV2A") (pin "1") (pinfunction "1_1") (pintype "unspecified"))
      (node (ref "U10") (pin "40") (pinfunction "CA1_40") (pintype "unspecified"))
    )
    (net (code "78") (name "VIA2-CA2") (class "Default")
      (node (ref "HV2A") (pin "2") (pinfunction "2_2") (pintype "unspecified"))
      (node (ref "U10") (pin "39") (pinfunction "CA2_39") (pintype "unspecified"))
    )
    (net (code "79") (name "VIA2-CB1") (class "Default")
      (node (ref "HV2B") (pin "9") (pinfunction "9_9") (pintype "unspecified"))
      (node (ref "U10") (pin "18") (pinfunction "CB1_18") (pintype "unspecified"))
    )
    (net (code "80") (name "VIA2-CB2") (class "Default")
      (node (ref "HV2B") (pin "10") (pinfunction "10_10") (pintype "unspecified"))
      (node (ref "U10") (pin "19") (pinfunction "CB2_19") (pintype "unspecified"))
    )
    (net (code "81") (name "VIA2-PA0") (class "Default")
      (node (ref "HV2A") (pin "3") (pinfunction "3_3") (pintype "unspecified"))
      (node (ref "U10") (pin "2") (pinfunction "PA0_2") (pintype "unspecified"))
    )
    (net (code "82") (name "VIA2-PA1") (class "Default")
      (node (ref "HV2A") (pin "4") (pinfunction "4_4") (pintype "unspecified"))
      (node (ref "U10") (pin "3") (pinfunction "PA1_3") (pintype "unspecified"))
    )
    (net (code "83") (name "VIA2-PA2") (class "Default")
      (node (ref "HV2A") (pin "5") (pinfunction "5_5") (pintype "unspecified"))
      (node (ref "U10") (pin "4") (pinfunction "PA2_4") (pintype "unspecified"))
    )
    (net (code "84") (name "VIA2-PA3") (class "Default")
      (node (ref "HV2A") (pin "6") (pinfunction "6_6") (pintype "unspecified"))
      (node (ref "U10") (pin "5") (pinfunction "PA3_5") (pintype "unspecified"))
    )
    (net (code "85") (name "VIA2-PA4") (class "Default")
      (node (ref "HV2A") (pin "7") (pinfunction "7_7") (pintype "unspecified"))
      (node (ref "U10") (pin "6") (pinfunction "PA4_6") (pintype "unspecified"))
    )
    (net (code "86") (name "VIA2-PA5") (class "Default")
      (node (ref "HV2A") (pin "8") (pinfunction "8_8") (pintype "unspecified"))
      (node (ref "U10") (pin "7") (pinfunction "PA5_7") (pintype "unspecified"))
    )
    (net (code "87") (name "VIA2-PA6") (class "Default")
      (node (ref "HV2A") (pin "9") (pinfunction "9_9") (pintype "unspecified"))
      (node (ref "U10") (pin "8") (pinfunction "PA6_8") (pintype "unspecified"))
    )
    (net (code "88") (name "VIA2-PA7") (class "Default")
      (node (ref "HV2A") (pin "10") (pinfunction "10_10") (pintype "unspecified"))
      (node (ref "U10") (pin "9") (pinfunction "PA7_9") (pintype "unspecified"))
    )
    (net (code "89") (name "VIA2-PB0") (class "Default")
      (node (ref "HV2B") (pin "1") (pinfunction "1_1") (pintype "unspecified"))
      (node (ref "U10") (pin "10") (pinfunction "PB0_10") (pintype "unspecified"))
    )
    (net (code "90") (name "VIA2-PB1") (class "Default")
      (node (ref "HV2B") (pin "2") (pinfunction "2_2") (pintype "unspecified"))
      (node (ref "U10") (pin "11") (pinfunction "PB1_11") (pintype "unspecified"))
    )
    (net (code "91") (name "VIA2-PB2") (class "Default")
      (node (ref "HV2B") (pin "3") (pinfunction "3_3") (pintype "unspecified"))
      (node (ref "U10") (pin "12") (pinfunction "PB2_12") (pintype "unspecified"))
    )
    (net (code "92") (name "VIA2-PB3") (class "Default")
      (node (ref "HV2B") (pin "4") (pinfunction "4_4") (pintype "unspecified"))
      (node (ref "U10") (pin "13") (pinfunction "PB3_13") (pintype "unspecified"))
    )
    (net (code "93") (name "VIA2-PB4") (class "Default")
      (node (ref "HV2B") (pin "5") (pinfunction "5_5") (pintype "unspecified"))
      (node (ref "U10") (pin "14") (pinfunction "PB4_14") (pintype "unspecified"))
    )
    (net (code "94") (name "VIA2-PB5") (class "Default")
      (node (ref "HV2B") (pin "6") (pinfunction "6_6") (pintype "unspecified"))
      (node (ref "U10") (pin "15") (pinfunction "PB5_15") (pintype "unspecified"))
    )
    (net (code "95") (name "VIA2-PB6") (class "Default")
      (node (ref "HV2B") (pin "7") (pinfunction "7_7") (pintype "unspecified"))
      (node (ref "U10") (pin "16") (pinfunction "PB6_16") (pintype "unspecified"))
    )
    (net (code "96") (name "VIA2-PB7") (class "Default")
      (node (ref "HV2B") (pin "8") (pinfunction "8_8") (pintype "unspecified"))
      (node (ref "U10") (pin "17") (pinfunction "PB7_17") (pintype "unspecified"))
    )
    (net (code "97") (name "VIA2_CS") (class "Default")
      (node (ref "U10") (pin "23") (pinfunction "CS1B_23") (pintype "unspecified"))
      (node (ref "U4") (pin "18") (pinfunction "I/O/Q_18") (pintype "unspecified"))
    )
    (net (code "98") (name "WE") (class "Default")
      (node (ref "U3") (pin "27") (pinfunction "WE_27") (pintype "input"))
      (node (ref "U4") (pin "23") (pinfunction "I/O/Q_23") (pintype "unspecified"))
    )
    (net (code "99") (name "XPN_CS") (class "Default")
      (node (ref "HXPN1") (pin "24") (pinfunction "24_24") (pintype "unspecified"))
      (node (ref "U4") (pin "20") (pinfunction "I/O/Q_20") (pintype "unspecified"))
    )
    (net (code "100") (name "unconnected-(HXPN1-Pad28)") (class "Default")
      (node (ref "HXPN1") (pin "28") (pinfunction "28_28") (pintype "unspecified+no_connect"))
    )
    (net (code "101") (name "unconnected-(SW1-Pad2)") (class "Default")
      (node (ref "SW1") (pin "2") (pinfunction "2_2") (pintype "unspecified+no_connect"))
    )
    (net (code "102") (name "unconnected-(SW1-Pad4)") (class "Default")
      (node (ref "SW1") (pin "4") (pinfunction "4_4") (pintype "unspecified+no_connect"))
    )
    (net (code "103") (name "unconnected-(U1-MLB-Pad5)") (class "Default")
      (node (ref "U1") (pin "5") (pinfunction "MLB_5") (pintype "output+no_connect"))
    )
    (net (code "104") (name "unconnected-(U1-NC-Pad35)") (class "Default")
      (node (ref "U1") (pin "35") (pinfunction "NC_35") (pintype "unspecified+no_connect"))
    )
    (net (code "105") (name "unconnected-(U1-PHI1-Pad3)") (class "Default")
      (node (ref "U1") (pin "3") (pinfunction "PHI1_3") (pintype "output+no_connect"))
    )
    (net (code "106") (name "unconnected-(U1-SYNC-Pad7)") (class "Default")
      (node (ref "U1") (pin "7") (pinfunction "SYNC_7") (pintype "output+no_connect"))
    )
    (net (code "107") (name "unconnected-(U1-VPB-Pad1)") (class "Default")
      (node (ref "U1") (pin "1") (pinfunction "VPB_1") (pintype "output+no_connect"))
    )
    (net (code "108") (name "unconnected-(U5-1Y-Pad6)") (class "Default")
      (node (ref "U5") (pin "6") (pinfunction "1Y_6") (pintype "unspecified+no_connect"))
    )
    (net (code "109") (name "unconnected-(U5-NC-Pad11)") (class "Default")
      (node (ref "U5") (pin "11") (pinfunction "NC_11") (pintype "unspecified+no_connect"))
    )
    (net (code "110") (name "unconnected-(U5-NC{slash}2-Pad3)") (class "Default")
      (node (ref "U5") (pin "3") (pinfunction "NC/2_3") (pintype "unspecified+no_connect"))
    )
    (net (code "111") (name "unconnected-(U7--DTR-Pad11)") (class "Default")
      (node (ref "U7") (pin "11") (pinfunction "-DTR_11") (pintype "unspecified+no_connect"))
    )
    (net (code "112") (name "unconnected-(U7-RxC-Pad5)") (class "Default")
      (node (ref "U7") (pin "5") (pinfunction "RxC_5") (pintype "unspecified+no_connect"))
    )
    (net (code "113") (name "unconnected-(U7-XTLO-Pad7)") (class "Default")
      (node (ref "U7") (pin "7") (pinfunction "XTLO_7") (pintype "unspecified+no_connect"))
    )
    (net (code "114") (name "unconnected-(U8-CBUS2-Pad7)") (class "Default")
      (node (ref "U8") (pin "7") (pinfunction "CBUS2_7") (pintype "bidirectional+no_connect"))
    )
    (net (code "115") (name "unconnected-(U8-CBUS3-Pad16)") (class "Default")
      (node (ref "U8") (pin "16") (pinfunction "CBUS3_16") (pintype "bidirectional+no_connect"))
    )
    (net (code "116") (name "unconnected-(X1-NC-Pad1)") (class "Default")
      (node (ref "X1") (pin "1") (pinfunction "NC_1") (pintype "bidirectional+no_connect"))
    )
    (net (code "117") (name "unconnected-(X2-NC-Pad1)") (class "Default")
      (node (ref "X2") (pin "1") (pinfunction "NC_1") (pintype "bidirectional+no_connect"))
    )
  )
)
